# voltage-booster-mic2145.net
KiCad netlist of a schematic drawn in EAGLE
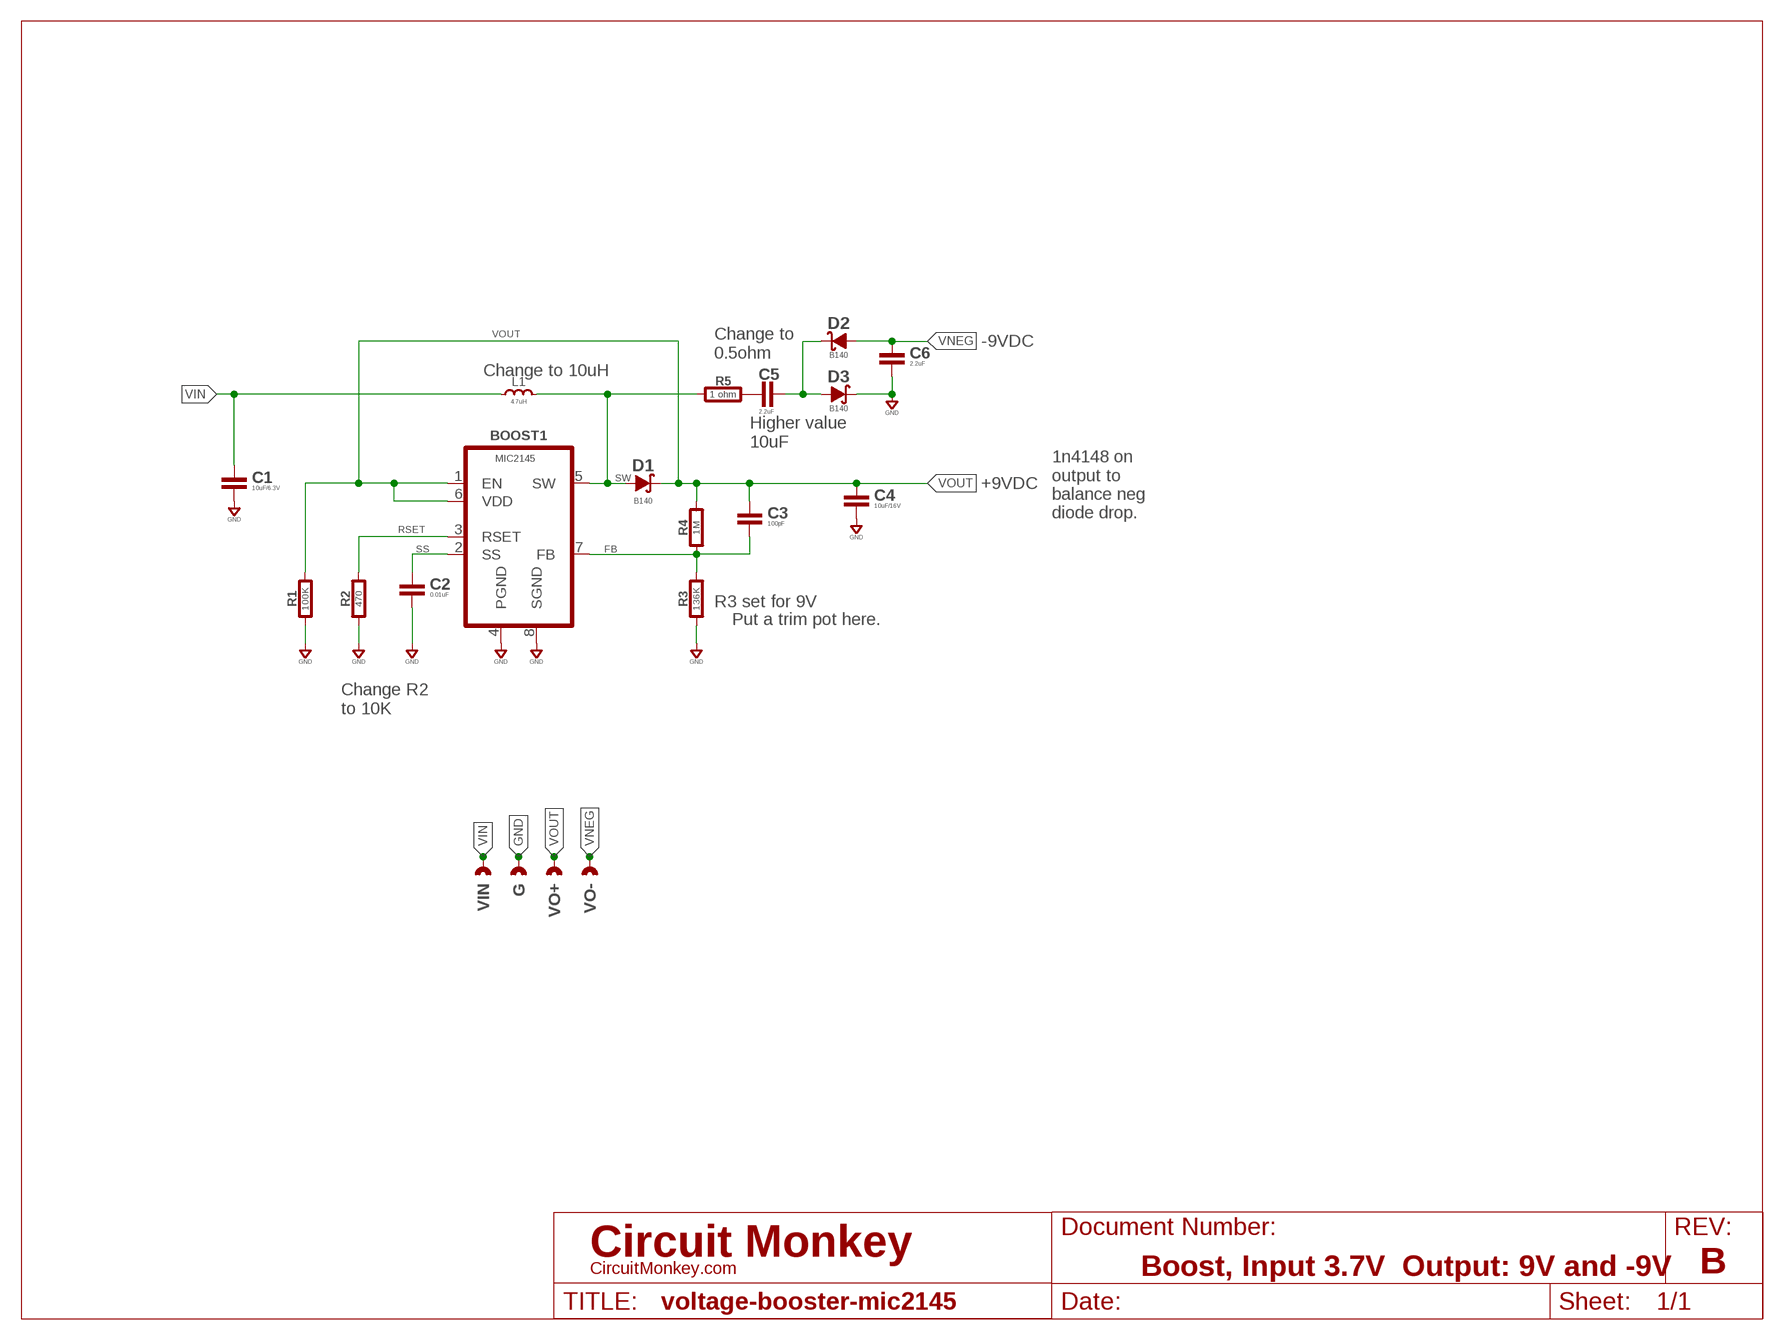
[diagram p0: schematic, sheet 1]

(export (version "E")
  (design (tool "Eeschema 10.0.6"))
  (components
    (comp (ref "BOOST1")
      (value "MIC2145")
      (footprint "eagle-import:MSOP8-0.65")
      (fields (field (name "MFR") "Micrel") (field (name "MPN") "MIC2145YMM"))
      (libsource (lib "eagle-import") (part "BOOST-MIC2145-MSOP"))
    )
    (comp (ref "C1")
      (value "10uF/6.3V")
      (footprint "eagle-import:0603-CAP")
      (libsource (lib "eagle-import") (part "CAPACITOR0603"))
    )
    (comp (ref "C2")
      (value "0.01uF")
      (footprint "eagle-import:0603-CAP")
      (libsource (lib "eagle-import") (part "CAPACITOR0603"))
    )
    (comp (ref "C3")
      (value "100pF")
      (footprint "eagle-import:0603-CAP")
      (libsource (lib "eagle-import") (part "CAPACITOR0603"))
    )
    (comp (ref "C4")
      (value "10uF/16V")
      (footprint "eagle-import:0603-CAP")
      (libsource (lib "eagle-import") (part "CAPACITOR0603"))
    )
    (comp (ref "C5")
      (value "2.2uF")
      (footprint "eagle-import:0603-CAP")
      (libsource (lib "eagle-import") (part "CAPACITOR0603"))
    )
    (comp (ref "C6")
      (value "2.2uF")
      (footprint "eagle-import:0603-CAP")
      (libsource (lib "eagle-import") (part "CAPACITOR0603"))
    )
    (comp (ref "D1")
      (value "B140")
      (footprint "eagle-import:SMA")
      (fields (field (name "MFR") "Vishay/Various"))
      (libsource (lib "eagle-import") (part "SCHOTTKYB140"))
    )
    (comp (ref "D2")
      (value "B140")
      (footprint "eagle-import:SMA")
      (fields (field (name "MFR") "Vishay/Various"))
      (libsource (lib "eagle-import") (part "SCHOTTKYB140"))
    )
    (comp (ref "D3")
      (value "B140")
      (footprint "eagle-import:SMA")
      (fields (field (name "MFR") "Vishay/Various"))
      (libsource (lib "eagle-import") (part "SCHOTTKYB140"))
    )
    (comp (ref "G")
      (value "CAST-01X12.54MM")
      (footprint "eagle-import:CAST01-2.54MM")
      (libsource (lib "eagle-import") (part "CAST-01X12.54MM"))
    )
    (comp (ref "L1")
      (value "4.7uH")
      (footprint "eagle-import:IND-SRN5040")
      (fields (field (name "MFR") "Bourns") (field (name "MPN") "SRN5040"))
      (libsource (lib "eagle-import") (part "INDUCTORSMD-05X04MM"))
    )
    (comp (ref "R1")
      (value "100K")
      (footprint "eagle-import:0603-RES")
      (libsource (lib "eagle-import") (part "RESISTOR0603"))
    )
    (comp (ref "R2")
      (value "470")
      (footprint "eagle-import:0603-RES")
      (libsource (lib "eagle-import") (part "RESISTOR0603"))
    )
    (comp (ref "R3")
      (value "136K")
      (footprint "eagle-import:0603-RES")
      (libsource (lib "eagle-import") (part "RESISTOR0603"))
    )
    (comp (ref "R4")
      (value "1M")
      (footprint "eagle-import:0603-RES")
      (libsource (lib "eagle-import") (part "RESISTOR0603"))
    )
    (comp (ref "R5")
      (value "1 ohm")
      (footprint "eagle-import:0603-RES")
      (libsource (lib "eagle-import") (part "RESISTOR0603"))
    )
    (comp (ref "VIN")
      (value "CAST-01X12.54MM")
      (footprint "eagle-import:CAST01-2.54MM")
      (libsource (lib "eagle-import") (part "CAST-01X12.54MM"))
    )
    (comp (ref "VO+")
      (value "CAST-01X12.54MM")
      (footprint "eagle-import:CAST01-2.54MM")
      (libsource (lib "eagle-import") (part "CAST-01X12.54MM"))
    )
    (comp (ref "VO-")
      (value "CAST-01X12.54MM")
      (footprint "eagle-import:CAST01-2.54MM")
      (libsource (lib "eagle-import") (part "CAST-01X12.54MM"))
    )
  )
  (nets
    (net (code "1") (name "/FB") (class "Default")
      (node (ref "BOOST1") (pin "7") (pinfunction "FB_7") (pintype "bidirectional"))
      (node (ref "C3") (pin "2") (pinfunction "2_2") (pintype "passive"))
      (node (ref "R3") (pin "2") (pinfunction "2_2") (pintype "passive"))
      (node (ref "R4") (pin "1") (pinfunction "1_1") (pintype "passive"))
    )
    (net (code "2") (name "/RSET") (class "Default")
      (node (ref "BOOST1") (pin "3") (pinfunction "RSET_3") (pintype "bidirectional"))
      (node (ref "R2") (pin "2") (pinfunction "2_2") (pintype "passive"))
    )
    (net (code "3") (name "/SS") (class "Default")
      (node (ref "BOOST1") (pin "2") (pinfunction "SS_2") (pintype "bidirectional"))
      (node (ref "C2") (pin "1") (pinfunction "1_1") (pintype "passive"))
    )
    (net (code "4") (name "/SW") (class "Default")
      (node (ref "BOOST1") (pin "5") (pinfunction "SW_5") (pintype "bidirectional"))
      (node (ref "D1") (pin "A") (pinfunction "A_A") (pintype "passive"))
      (node (ref "L1") (pin "1") (pinfunction "P$1_1") (pintype "passive"))
      (node (ref "R5") (pin "1") (pinfunction "1_1") (pintype "passive"))
    )
    (net (code "5") (name "GND") (class "Default")
      (node (ref "BOOST1") (pin "4") (pinfunction "PGND_4") (pintype "bidirectional"))
      (node (ref "BOOST1") (pin "8") (pinfunction "SGND_8") (pintype "bidirectional"))
      (node (ref "C1") (pin "2") (pinfunction "2_2") (pintype "passive"))
      (node (ref "C2") (pin "2") (pinfunction "2_2") (pintype "passive"))
      (node (ref "C4") (pin "2") (pinfunction "2_2") (pintype "passive"))
      (node (ref "C6") (pin "2") (pinfunction "2_2") (pintype "passive"))
      (node (ref "D3") (pin "K") (pinfunction "K_K") (pintype "passive"))
      (node (ref "G") (pin "1") (pinfunction "1_1") (pintype "bidirectional"))
      (node (ref "R1") (pin "1") (pinfunction "1_1") (pintype "passive"))
      (node (ref "R2") (pin "1") (pinfunction "1_1") (pintype "passive"))
      (node (ref "R3") (pin "1") (pinfunction "1_1") (pintype "passive"))
    )
    (net (code "6") (name "Net-(C5-Pad1)") (class "Default")
      (node (ref "C5") (pin "1") (pinfunction "1_1") (pintype "passive"))
      (node (ref "R5") (pin "2") (pinfunction "2_2") (pintype "passive"))
    )
    (net (code "7") (name "Net-(C5-Pad2)") (class "Default")
      (node (ref "C5") (pin "2") (pinfunction "2_2") (pintype "passive"))
      (node (ref "D2") (pin "K") (pinfunction "K_K") (pintype "passive"))
      (node (ref "D3") (pin "A") (pinfunction "A_A") (pintype "passive"))
    )
    (net (code "8") (name "VIN") (class "Default")
      (node (ref "C1") (pin "1") (pinfunction "1_1") (pintype "passive"))
      (node (ref "L1") (pin "2") (pinfunction "P$2_2") (pintype "passive"))
      (node (ref "VIN") (pin "1") (pinfunction "1_1") (pintype "bidirectional"))
    )
    (net (code "9") (name "VNEG") (class "Default")
      (node (ref "C6") (pin "1") (pinfunction "1_1") (pintype "passive"))
      (node (ref "D2") (pin "A") (pinfunction "A_A") (pintype "passive"))
      (node (ref "VO-") (pin "1") (pinfunction "1_1") (pintype "bidirectional"))
    )
    (net (code "10") (name "VOUT") (class "Default")
      (node (ref "BOOST1") (pin "1") (pinfunction "EN_1") (pintype "bidirectional"))
      (node (ref "BOOST1") (pin "6") (pinfunction "VDD_6") (pintype "bidirectional"))
      (node (ref "C3") (pin "1") (pinfunction "1_1") (pintype "passive"))
      (node (ref "C4") (pin "1") (pinfunction "1_1") (pintype "passive"))
      (node (ref "D1") (pin "K") (pinfunction "K_K") (pintype "passive"))
      (node (ref "R1") (pin "2") (pinfunction "2_2") (pintype "passive"))
      (node (ref "R4") (pin "2") (pinfunction "2_2") (pintype "passive"))
      (node (ref "VO+") (pin "1") (pinfunction "1_1") (pintype "bidirectional"))
    )
  )
)
